# DBL_165_ShiftIn_Red_-_TestButtonsPlate.net
KiCad netlist of a schematic drawn in Altium Designer
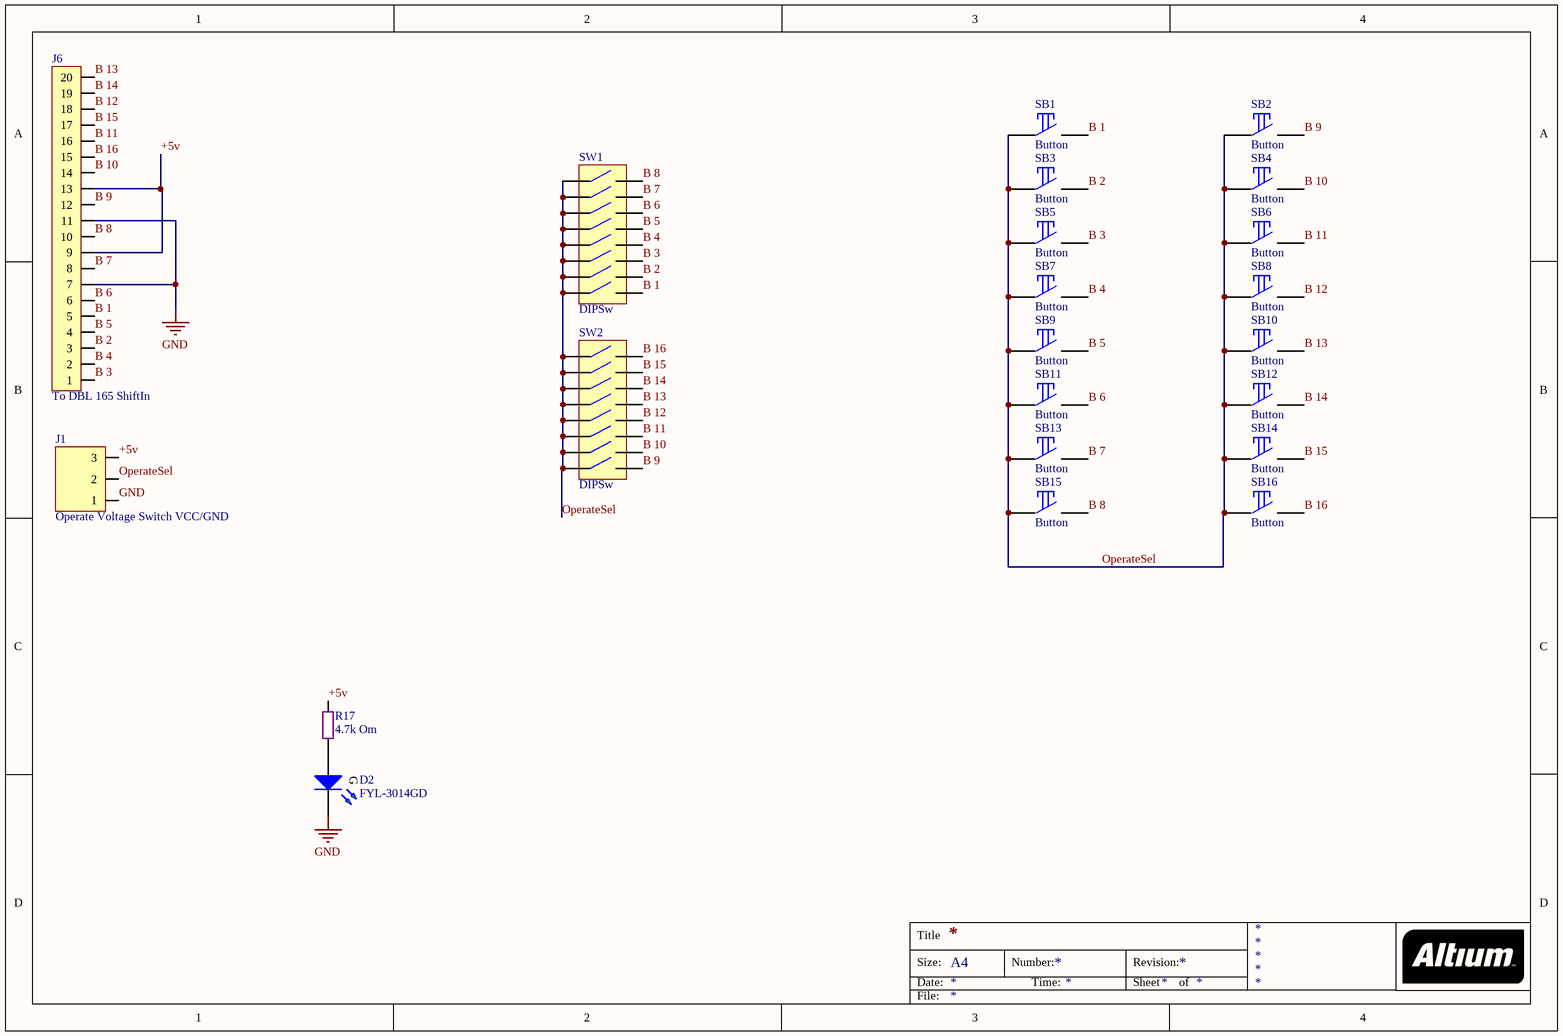
[diagram p0: DBL 165 ShiftIn Red - TestButtonsPlate.SchDoc]

(export (version "E")
  (design (tool "Eeschema 10.0.6"))
  (components
    (comp (ref "D2")
      (value "FYL-3014GD")
      (footprint "LED:LED Round 3mm Green")
      (description "2.1v 10mA, 15-30mCd")
      (libsource (lib "LED") (part "Led Round 3mm Green"))
    )
    (comp (ref "J1")
      (value "Operate Voltage Switch VCC/GND")
      (footprint "Connector:Line 2.54 X 3")
      (description "Vert, Sgl line, Male")
      (libsource (lib "Connector") (part "PLS-3"))
    )
    (comp (ref "J6")
      (value "To DBL 165 ShiftIn")
      (footprint "Connector:LINE 2.54 x 20D (2 x 10) - BH")
      (description "Vert, Dbl line, Male")
      (libsource (lib "Connector") (part "PLD-20 (2 x 10)"))
    )
    (comp (ref "R17")
      (value "4.7k Om")
      (footprint "PassiveComponents:SMD 0805 (2012)")
      (libsource (lib "PassiveComponents") (part "Res All Types"))
    )
    (comp (ref "SB1")
      (value "Button")
      (footprint "Relay:Switch Button 2P")
      (description "Tact button")
      (libsource (lib "Relay") (part "Button"))
    )
    (comp (ref "SB2")
      (value "Button")
      (footprint "Relay:Switch Button 2P")
      (description "Tact button")
      (libsource (lib "Relay") (part "Button"))
    )
    (comp (ref "SB3")
      (value "Button")
      (footprint "Relay:Switch Button 2P")
      (description "Tact button")
      (libsource (lib "Relay") (part "Button"))
    )
    (comp (ref "SB4")
      (value "Button")
      (footprint "Relay:Switch Button 2P")
      (description "Tact button")
      (libsource (lib "Relay") (part "Button"))
    )
    (comp (ref "SB5")
      (value "Button")
      (footprint "Relay:Switch Button 2P")
      (description "Tact button")
      (libsource (lib "Relay") (part "Button"))
    )
    (comp (ref "SB6")
      (value "Button")
      (footprint "Relay:Switch Button 2P")
      (description "Tact button")
      (libsource (lib "Relay") (part "Button"))
    )
    (comp (ref "SB7")
      (value "Button")
      (footprint "Relay:Switch Button 2P")
      (description "Tact button")
      (libsource (lib "Relay") (part "Button"))
    )
    (comp (ref "SB8")
      (value "Button")
      (footprint "Relay:Switch Button 2P")
      (description "Tact button")
      (libsource (lib "Relay") (part "Button"))
    )
    (comp (ref "SB9")
      (value "Button")
      (footprint "Relay:Switch Button 2P")
      (description "Tact button")
      (libsource (lib "Relay") (part "Button"))
    )
    (comp (ref "SB10")
      (value "Button")
      (footprint "Relay:Switch Button 2P")
      (description "Tact button")
      (libsource (lib "Relay") (part "Button"))
    )
    (comp (ref "SB11")
      (value "Button")
      (footprint "Relay:Switch Button 2P")
      (description "Tact button")
      (libsource (lib "Relay") (part "Button"))
    )
    (comp (ref "SB12")
      (value "Button")
      (footprint "Relay:Switch Button 2P")
      (description "Tact button")
      (libsource (lib "Relay") (part "Button"))
    )
    (comp (ref "SB13")
      (value "Button")
      (footprint "Relay:Switch Button 2P")
      (description "Tact button")
      (libsource (lib "Relay") (part "Button"))
    )
    (comp (ref "SB14")
      (value "Button")
      (footprint "Relay:Switch Button 2P")
      (description "Tact button")
      (libsource (lib "Relay") (part "Button"))
    )
    (comp (ref "SB15")
      (value "Button")
      (footprint "Relay:Switch Button 2P")
      (description "Tact button")
      (libsource (lib "Relay") (part "Button"))
    )
    (comp (ref "SB16")
      (value "Button")
      (footprint "Relay:Switch Button 2P")
      (description "Tact button")
      (libsource (lib "Relay") (part "Button"))
    )
    (comp (ref "SW1")
      (value "DIPSw")
      (footprint "Relay:DIP Switch 8p")
      (libsource (lib "Relay") (part "DIP Switch 8pos"))
    )
    (comp (ref "SW2")
      (value "DIPSw")
      (footprint "Relay:DIP Switch 8p")
      (libsource (lib "Relay") (part "DIP Switch 8pos"))
    )
  )
  (nets
    (net (code "1") (name "/+5v") (class "Default")
      (node (ref "J1") (pin "3") (pinfunction "3_3") (pintype "passive"))
      (node (ref "J6") (pin "13") (pinfunction "13_13") (pintype "passive"))
      (node (ref "J6") (pin "9") (pinfunction "9_9") (pintype "passive"))
      (node (ref "R17") (pin "1") (pinfunction "1_1") (pintype "passive"))
    )
    (net (code "2") (name "/B 1") (class "Default")
      (node (ref "J6") (pin "5") (pinfunction "5_5") (pintype "passive"))
      (node (ref "SB1") (pin "2") (pinfunction "2_2") (pintype "passive"))
      (node (ref "SW1") (pin "16") (pinfunction "16_16") (pintype "passive"))
    )
    (net (code "3") (name "/B 2") (class "Default")
      (node (ref "J6") (pin "3") (pinfunction "3_3") (pintype "passive"))
      (node (ref "SB3") (pin "2") (pinfunction "2_2") (pintype "passive"))
      (node (ref "SW1") (pin "14") (pinfunction "14_14") (pintype "passive"))
    )
    (net (code "4") (name "/B 3") (class "Default")
      (node (ref "J6") (pin "1") (pinfunction "1_1") (pintype "passive"))
      (node (ref "SB5") (pin "2") (pinfunction "2_2") (pintype "passive"))
      (node (ref "SW1") (pin "12") (pinfunction "12_12") (pintype "passive"))
    )
    (net (code "5") (name "/B 4") (class "Default")
      (node (ref "J6") (pin "2") (pinfunction "2_2") (pintype "passive"))
      (node (ref "SB7") (pin "2") (pinfunction "2_2") (pintype "passive"))
      (node (ref "SW1") (pin "10") (pinfunction "10_10") (pintype "passive"))
    )
    (net (code "6") (name "/B 5") (class "Default")
      (node (ref "J6") (pin "4") (pinfunction "4_4") (pintype "passive"))
      (node (ref "SB9") (pin "2") (pinfunction "2_2") (pintype "passive"))
      (node (ref "SW1") (pin "8") (pinfunction "8_8") (pintype "passive"))
    )
    (net (code "7") (name "/B 6") (class "Default")
      (node (ref "J6") (pin "6") (pinfunction "6_6") (pintype "passive"))
      (node (ref "SB11") (pin "2") (pinfunction "2_2") (pintype "passive"))
      (node (ref "SW1") (pin "6") (pinfunction "6_6") (pintype "passive"))
    )
    (net (code "8") (name "/B 7") (class "Default")
      (node (ref "J6") (pin "8") (pinfunction "8_8") (pintype "passive"))
      (node (ref "SB13") (pin "2") (pinfunction "2_2") (pintype "passive"))
      (node (ref "SW1") (pin "4") (pinfunction "4_4") (pintype "passive"))
    )
    (net (code "9") (name "/B 8") (class "Default")
      (node (ref "J6") (pin "10") (pinfunction "10_10") (pintype "passive"))
      (node (ref "SB15") (pin "2") (pinfunction "2_2") (pintype "passive"))
      (node (ref "SW1") (pin "2") (pinfunction "2_2") (pintype "passive"))
    )
    (net (code "10") (name "/B 9") (class "Default")
      (node (ref "J6") (pin "12") (pinfunction "12_12") (pintype "passive"))
      (node (ref "SB2") (pin "2") (pinfunction "2_2") (pintype "passive"))
      (node (ref "SW2") (pin "16") (pinfunction "16_16") (pintype "passive"))
    )
    (net (code "11") (name "/B 10") (class "Default")
      (node (ref "J6") (pin "14") (pinfunction "14_14") (pintype "passive"))
      (node (ref "SB4") (pin "2") (pinfunction "2_2") (pintype "passive"))
      (node (ref "SW2") (pin "14") (pinfunction "14_14") (pintype "passive"))
    )
    (net (code "12") (name "/B 11") (class "Default")
      (node (ref "J6") (pin "16") (pinfunction "16_16") (pintype "passive"))
      (node (ref "SB6") (pin "2") (pinfunction "2_2") (pintype "passive"))
      (node (ref "SW2") (pin "12") (pinfunction "12_12") (pintype "passive"))
    )
    (net (code "13") (name "/B 12") (class "Default")
      (node (ref "J6") (pin "18") (pinfunction "18_18") (pintype "passive"))
      (node (ref "SB8") (pin "2") (pinfunction "2_2") (pintype "passive"))
      (node (ref "SW2") (pin "10") (pinfunction "10_10") (pintype "passive"))
    )
    (net (code "14") (name "/B 13") (class "Default")
      (node (ref "J6") (pin "20") (pinfunction "20_20") (pintype "passive"))
      (node (ref "SB10") (pin "2") (pinfunction "2_2") (pintype "passive"))
      (node (ref "SW2") (pin "8") (pinfunction "8_8") (pintype "passive"))
    )
    (net (code "15") (name "/B 14") (class "Default")
      (node (ref "J6") (pin "19") (pinfunction "19_19") (pintype "passive"))
      (node (ref "SB12") (pin "2") (pinfunction "2_2") (pintype "passive"))
      (node (ref "SW2") (pin "6") (pinfunction "6_6") (pintype "passive"))
    )
    (net (code "16") (name "/B 15") (class "Default")
      (node (ref "J6") (pin "17") (pinfunction "17_17") (pintype "passive"))
      (node (ref "SB14") (pin "2") (pinfunction "2_2") (pintype "passive"))
      (node (ref "SW2") (pin "4") (pinfunction "4_4") (pintype "passive"))
    )
    (net (code "17") (name "/B 16") (class "Default")
      (node (ref "J6") (pin "15") (pinfunction "15_15") (pintype "passive"))
      (node (ref "SB16") (pin "2") (pinfunction "2_2") (pintype "passive"))
      (node (ref "SW2") (pin "2") (pinfunction "2_2") (pintype "passive"))
    )
    (net (code "18") (name "/OperateSel") (class "Default")
      (node (ref "J1") (pin "2") (pinfunction "2_2") (pintype "passive"))
      (node (ref "SB1") (pin "1") (pinfunction "1_1") (pintype "passive"))
      (node (ref "SB10") (pin "1") (pinfunction "1_1") (pintype "passive"))
      (node (ref "SB11") (pin "1") (pinfunction "1_1") (pintype "passive"))
      (node (ref "SB12") (pin "1") (pinfunction "1_1") (pintype "passive"))
      (node (ref "SB13") (pin "1") (pinfunction "1_1") (pintype "passive"))
      (node (ref "SB14") (pin "1") (pinfunction "1_1") (pintype "passive"))
      (node (ref "SB15") (pin "1") (pinfunction "1_1") (pintype "passive"))
      (node (ref "SB16") (pin "1") (pinfunction "1_1") (pintype "passive"))
      (node (ref "SB2") (pin "1") (pinfunction "1_1") (pintype "passive"))
      (node (ref "SB3") (pin "1") (pinfunction "1_1") (pintype "passive"))
      (node (ref "SB4") (pin "1") (pinfunction "1_1") (pintype "passive"))
      (node (ref "SB5") (pin "1") (pinfunction "1_1") (pintype "passive"))
      (node (ref "SB6") (pin "1") (pinfunction "1_1") (pintype "passive"))
      (node (ref "SB7") (pin "1") (pinfunction "1_1") (pintype "passive"))
      (node (ref "SB8") (pin "1") (pinfunction "1_1") (pintype "passive"))
      (node (ref "SB9") (pin "1") (pinfunction "1_1") (pintype "passive"))
      (node (ref "SW1") (pin "1") (pinfunction "1_1") (pintype "passive"))
      (node (ref "SW1") (pin "11") (pinfunction "11_11") (pintype "passive"))
      (node (ref "SW1") (pin "13") (pinfunction "13_13") (pintype "passive"))
      (node (ref "SW1") (pin "15") (pinfunction "15_15") (pintype "passive"))
      (node (ref "SW1") (pin "3") (pinfunction "3_3") (pintype "passive"))
      (node (ref "SW1") (pin "5") (pinfunction "5_5") (pintype "passive"))
      (node (ref "SW1") (pin "7") (pinfunction "7_7") (pintype "passive"))
      (node (ref "SW1") (pin "9") (pinfunction "9_9") (pintype "passive"))
      (node (ref "SW2") (pin "1") (pinfunction "1_1") (pintype "passive"))
      (node (ref "SW2") (pin "11") (pinfunction "11_11") (pintype "passive"))
      (node (ref "SW2") (pin "13") (pinfunction "13_13") (pintype "passive"))
      (node (ref "SW2") (pin "15") (pinfunction "15_15") (pintype "passive"))
      (node (ref "SW2") (pin "3") (pinfunction "3_3") (pintype "passive"))
      (node (ref "SW2") (pin "5") (pinfunction "5_5") (pintype "passive"))
      (node (ref "SW2") (pin "7") (pinfunction "7_7") (pintype "passive"))
      (node (ref "SW2") (pin "9") (pinfunction "9_9") (pintype "passive"))
    )
    (net (code "19") (name "GND") (class "Default")
      (node (ref "D2") (pin "K") (pinfunction "K_K") (pintype "passive"))
      (node (ref "J1") (pin "1") (pinfunction "1_1") (pintype "passive"))
      (node (ref "J6") (pin "11") (pinfunction "11_11") (pintype "passive"))
      (node (ref "J6") (pin "7") (pinfunction "7_7") (pintype "passive"))
    )
    (net (code "20") (name "Net-(D2-PadA)") (class "Default")
      (node (ref "D2") (pin "A") (pinfunction "A_A") (pintype "passive"))
      (node (ref "R17") (pin "2") (pinfunction "2_2") (pintype "passive"))
    )
  )
)
